# ADC.net
KiCad netlist of a schematic drawn in Altium Designer
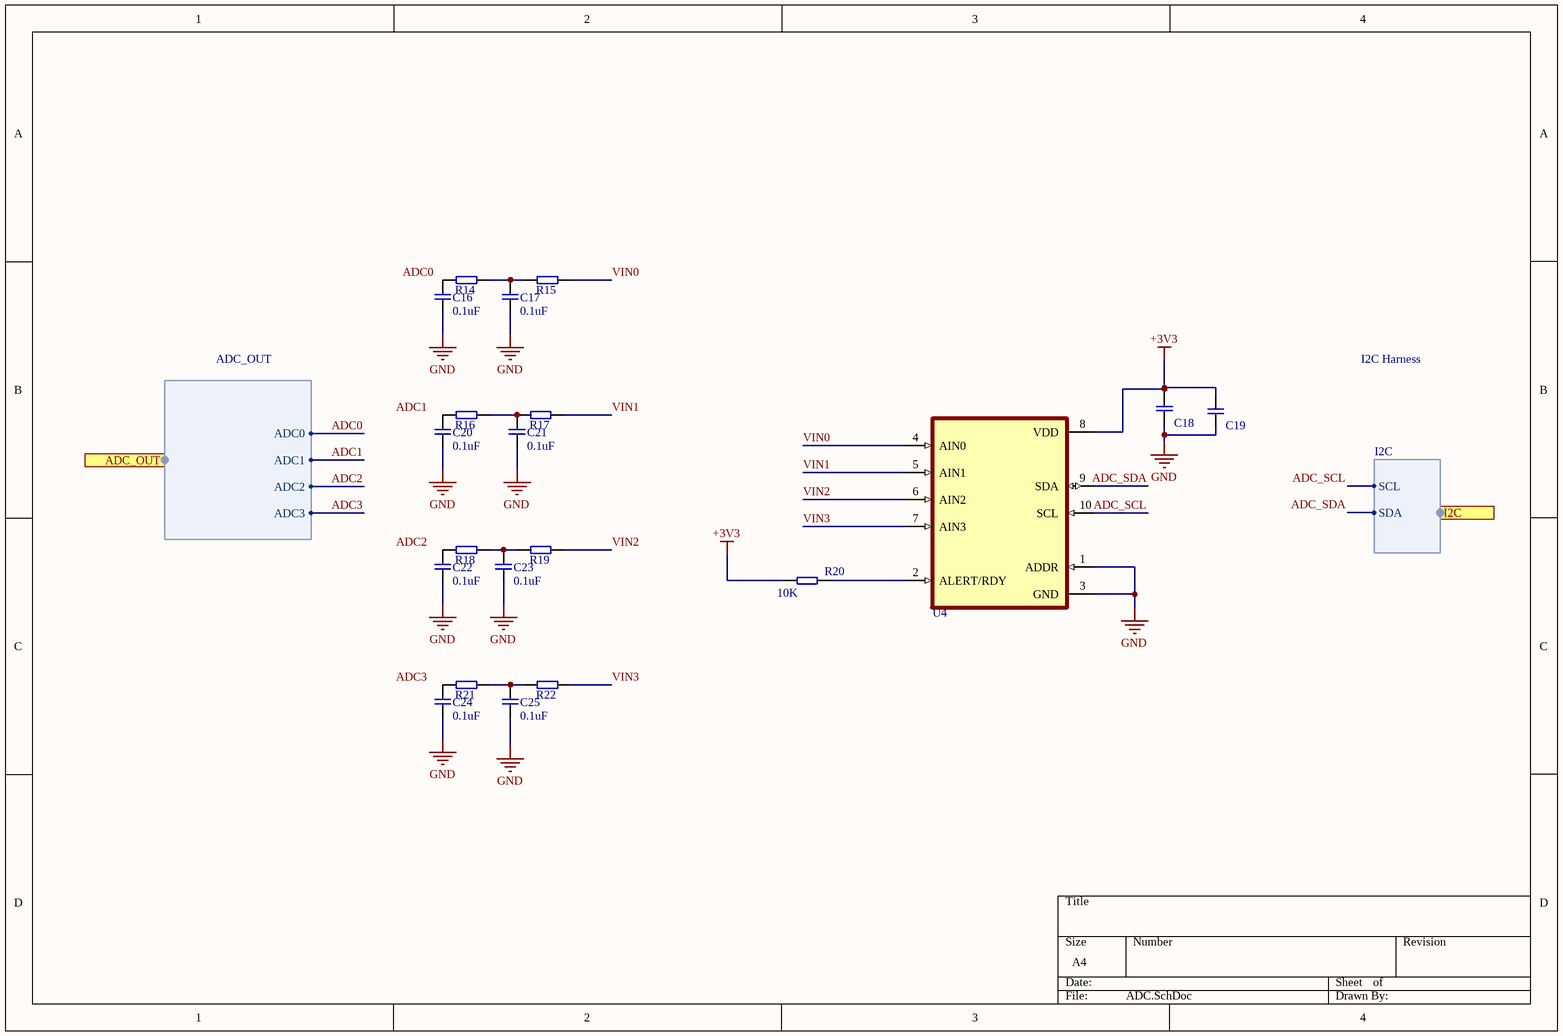
[diagram p0: ADC.SchDoc]

(export (version "E")
  (design (tool "Eeschema 10.0.6"))
  (components
    (comp (ref "C16")
      (value "0.1uF")
      (footprint "C0402")
      (description "CAP CER 0.1UF 10V X5R 0402")
      (fields (field (name "PART NUMBER") "C1005X5R1A104K050BA") (field (name "VOLTAGE") "10V"))
      (libsource (lib "anayurt") (part "CAP"))
    )
    (comp (ref "C17")
      (value "0.1uF")
      (footprint "C0402")
      (description "CAP CER 0.1UF 10V X5R 0402")
      (fields (field (name "PART NUMBER") "C1005X5R1A104K050BA") (field (name "VOLTAGE") "10V"))
      (libsource (lib "anayurt") (part "CAP"))
    )
    (comp (ref "C18")
      (value "1uF")
      (footprint "C0603")
      (description "CAP CER 1UF 16V X5R 0603")
      (fields (field (name "PART NUMBER") "GMC10X5R105K16NT") (field (name "VOLTAGE") "16V"))
      (libsource (lib "anayurt") (part "CAP"))
    )
    (comp (ref "C19")
      (value "10uF")
      (footprint "C0603")
      (description "CAP CER 10UF 16V X5R 0603")
      (fields (field (name "PART NUMBER") "GRT188R61C106KE13D") (field (name "VOLTAGE") "16V"))
      (libsource (lib "anayurt") (part "CAP"))
    )
    (comp (ref "C20")
      (value "0.1uF")
      (footprint "C0402")
      (description "CAP CER 0.1UF 10V X5R 0402")
      (fields (field (name "PART NUMBER") "C1005X5R1A104K050BA") (field (name "VOLTAGE") "10V"))
      (libsource (lib "anayurt") (part "CAP"))
    )
    (comp (ref "C21")
      (value "0.1uF")
      (footprint "C0402")
      (description "CAP CER 0.1UF 10V X5R 0402")
      (fields (field (name "PART NUMBER") "C1005X5R1A104K050BA") (field (name "VOLTAGE") "10V"))
      (libsource (lib "anayurt") (part "CAP"))
    )
    (comp (ref "C22")
      (value "0.1uF")
      (footprint "C0402")
      (description "CAP CER 0.1UF 10V X5R 0402")
      (fields (field (name "PART NUMBER") "C1005X5R1A104K050BA") (field (name "VOLTAGE") "10V"))
      (libsource (lib "anayurt") (part "CAP"))
    )
    (comp (ref "C23")
      (value "0.1uF")
      (footprint "C0402")
      (description "CAP CER 0.1UF 10V X5R 0402")
      (fields (field (name "PART NUMBER") "C1005X5R1A104K050BA") (field (name "VOLTAGE") "10V"))
      (libsource (lib "anayurt") (part "CAP"))
    )
    (comp (ref "C24")
      (value "0.1uF")
      (footprint "C0402")
      (description "CAP CER 0.1UF 10V X5R 0402")
      (fields (field (name "PART NUMBER") "C1005X5R1A104K050BA") (field (name "VOLTAGE") "10V"))
      (libsource (lib "anayurt") (part "CAP"))
    )
    (comp (ref "C25")
      (value "0.1uF")
      (footprint "C0402")
      (description "CAP CER 0.1UF 10V X5R 0402")
      (fields (field (name "PART NUMBER") "C1005X5R1A104K050BA") (field (name "VOLTAGE") "10V"))
      (libsource (lib "anayurt") (part "CAP"))
    )
    (comp (ref "R14")
      (value "200R")
      (footprint "R0402")
      (description "RES.(1005) 0402 200 Ohms 1% 1/16W 100PPM")
      (fields (field (name "PART NUMBER") "0402WGF2000TCE"))
      (libsource (lib "anayurt") (part "RES"))
    )
    (comp (ref "R15")
      (value "200R")
      (footprint "R0402")
      (description "RES.(1005) 0402 200 Ohms 1% 1/16W 100PPM")
      (fields (field (name "PART NUMBER") "0402WGF2000TCE"))
      (libsource (lib "anayurt") (part "RES"))
    )
    (comp (ref "R16")
      (value "200R")
      (footprint "R0402")
      (description "RES.(1005) 0402 200 Ohms 1% 1/16W 100PPM")
      (fields (field (name "PART NUMBER") "0402WGF2000TCE"))
      (libsource (lib "anayurt") (part "RES"))
    )
    (comp (ref "R17")
      (value "200R")
      (footprint "R0402")
      (description "RES.(1005) 0402 200 Ohms 1% 1/16W 100PPM")
      (fields (field (name "PART NUMBER") "0402WGF2000TCE"))
      (libsource (lib "anayurt") (part "RES"))
    )
    (comp (ref "R18")
      (value "200R")
      (footprint "R0402")
      (description "RES.(1005) 0402 200 Ohms 1% 1/16W 100PPM")
      (fields (field (name "PART NUMBER") "0402WGF2000TCE"))
      (libsource (lib "anayurt") (part "RES"))
    )
    (comp (ref "R19")
      (value "200R")
      (footprint "R0402")
      (description "RES.(1005) 0402 200 Ohms 1% 1/16W 100PPM")
      (fields (field (name "PART NUMBER") "0402WGF2000TCE"))
      (libsource (lib "anayurt") (part "RES"))
    )
    (comp (ref "R20")
      (value "10K")
      (footprint "R0603")
      (description "RES 10K OHM 1% 1/10W 0603")
      (fields (field (name "PART NUMBER") "RMCF0603FT10K0") (field (name "TOLERANCE") "1%"))
      (libsource (lib "anayurt") (part "RES"))
    )
    (comp (ref "R21")
      (value "200R")
      (footprint "R0402")
      (description "RES.(1005) 0402 200 Ohms 1% 1/16W 100PPM")
      (fields (field (name "PART NUMBER") "0402WGF2000TCE"))
      (libsource (lib "anayurt") (part "RES"))
    )
    (comp (ref "R22")
      (value "200R")
      (footprint "R0402")
      (description "RES.(1005) 0402 200 Ohms 1% 1/16W 100PPM")
      (fields (field (name "PART NUMBER") "0402WGF2000TCE"))
      (libsource (lib "anayurt") (part "RES"))
    )
    (comp (ref "U4")
      (value "ADS1115IDGST")
      (footprint "ADS1115IDGST")
      (description "IC ADC 16BIT SIGMA-DELTA 10VSSOP")
      (fields (field (name "MANUFACTURER") "Texas Instruments"))
      (libsource (lib "anayurt") (part "ADS1115IDGST"))
    )
  )
  (nets
    (net (code "3") (name "+3V3") (class "Default")
      (node (ref "C18") (pin "2") (pinfunction "2_2") (pintype "passive"))
      (node (ref "C19") (pin "2") (pinfunction "2_2") (pintype "passive"))
      (node (ref "R20") (pin "1") (pinfunction "1_1") (pintype "passive"))
      (node (ref "U4") (pin "8") (pinfunction "VDD_8") (pintype "power_in"))
    )
    (net (code "8") (name "/ADC_SCL") (class "Default")
      (node (ref "U4") (pin "10") (pinfunction "SCL_10") (pintype "input"))
    )
    (net (code "9") (name "/ADC_SDA") (class "Default")
      (node (ref "U4") (pin "9") (pinfunction "SDA_9") (pintype "bidirectional"))
    )
    (net (code "10") (name "/VIN0") (class "Default")
      (node (ref "R15") (pin "1") (pinfunction "1_1") (pintype "passive"))
      (node (ref "U4") (pin "4") (pinfunction "AIN0_4") (pintype "input"))
    )
    (net (code "11") (name "/VIN1") (class "Default")
      (node (ref "R17") (pin "1") (pinfunction "1_1") (pintype "passive"))
      (node (ref "U4") (pin "5") (pinfunction "AIN1_5") (pintype "input"))
    )
    (net (code "12") (name "/VIN2") (class "Default")
      (node (ref "R19") (pin "1") (pinfunction "1_1") (pintype "passive"))
      (node (ref "U4") (pin "6") (pinfunction "AIN2_6") (pintype "input"))
    )
    (net (code "13") (name "/VIN3") (class "Default")
      (node (ref "R22") (pin "1") (pinfunction "1_1") (pintype "passive"))
      (node (ref "U4") (pin "7") (pinfunction "AIN3_7") (pintype "input"))
    )
    (net (code "16") (name "GND") (class "Default")
      (node (ref "C16") (pin "1") (pinfunction "1_1") (pintype "passive"))
      (node (ref "C17") (pin "1") (pinfunction "1_1") (pintype "passive"))
      (node (ref "C18") (pin "1") (pinfunction "1_1") (pintype "passive"))
      (node (ref "C19") (pin "1") (pinfunction "1_1") (pintype "passive"))
      (node (ref "C20") (pin "1") (pinfunction "1_1") (pintype "passive"))
      (node (ref "C21") (pin "1") (pinfunction "1_1") (pintype "passive"))
      (node (ref "C22") (pin "1") (pinfunction "1_1") (pintype "passive"))
      (node (ref "C23") (pin "1") (pinfunction "1_1") (pintype "passive"))
      (node (ref "C24") (pin "1") (pinfunction "1_1") (pintype "passive"))
      (node (ref "C25") (pin "1") (pinfunction "1_1") (pintype "passive"))
      (node (ref "U4") (pin "1") (pinfunction "ADDR_1") (pintype "input"))
      (node (ref "U4") (pin "3") (pinfunction "GND_3") (pintype "power_in"))
    )
    (net (code "17") (name "Net-(C16-Pad2)") (class "Default")
      (node (ref "C16") (pin "2") (pinfunction "2_2") (pintype "passive"))
      (node (ref "R14") (pin "2") (pinfunction "2_2") (pintype "passive"))
    )
    (net (code "18") (name "Net-(C17-Pad2)") (class "Default")
      (node (ref "C17") (pin "2") (pinfunction "2_2") (pintype "passive"))
      (node (ref "R14") (pin "1") (pinfunction "1_1") (pintype "passive"))
      (node (ref "R15") (pin "2") (pinfunction "2_2") (pintype "passive"))
    )
    (net (code "19") (name "Net-(C20-Pad2)") (class "Default")
      (node (ref "C20") (pin "2") (pinfunction "2_2") (pintype "passive"))
      (node (ref "R16") (pin "2") (pinfunction "2_2") (pintype "passive"))
    )
    (net (code "20") (name "Net-(C21-Pad2)") (class "Default")
      (node (ref "C21") (pin "2") (pinfunction "2_2") (pintype "passive"))
      (node (ref "R16") (pin "1") (pinfunction "1_1") (pintype "passive"))
      (node (ref "R17") (pin "2") (pinfunction "2_2") (pintype "passive"))
    )
    (net (code "21") (name "Net-(C22-Pad2)") (class "Default")
      (node (ref "C22") (pin "2") (pinfunction "2_2") (pintype "passive"))
      (node (ref "R18") (pin "2") (pinfunction "2_2") (pintype "passive"))
    )
    (net (code "22") (name "Net-(C23-Pad2)") (class "Default")
      (node (ref "C23") (pin "2") (pinfunction "2_2") (pintype "passive"))
      (node (ref "R18") (pin "1") (pinfunction "1_1") (pintype "passive"))
      (node (ref "R19") (pin "2") (pinfunction "2_2") (pintype "passive"))
    )
    (net (code "23") (name "Net-(C24-Pad2)") (class "Default")
      (node (ref "C24") (pin "2") (pinfunction "2_2") (pintype "passive"))
      (node (ref "R21") (pin "2") (pinfunction "2_2") (pintype "passive"))
    )
    (net (code "24") (name "Net-(C25-Pad2)") (class "Default")
      (node (ref "C25") (pin "2") (pinfunction "2_2") (pintype "passive"))
      (node (ref "R21") (pin "1") (pinfunction "1_1") (pintype "passive"))
      (node (ref "R22") (pin "2") (pinfunction "2_2") (pintype "passive"))
    )
    (net (code "25") (name "Net-(U4-ALERT{slash}RDY)") (class "Default")
      (node (ref "R20") (pin "2") (pinfunction "2_2") (pintype "passive"))
      (node (ref "U4") (pin "2") (pinfunction "ALERT/RDY_2") (pintype "input"))
    )
  )
)
